# CMoy-Pro-V_0_0_1A.net
KiCad netlist of a schematic drawn in EAGLE
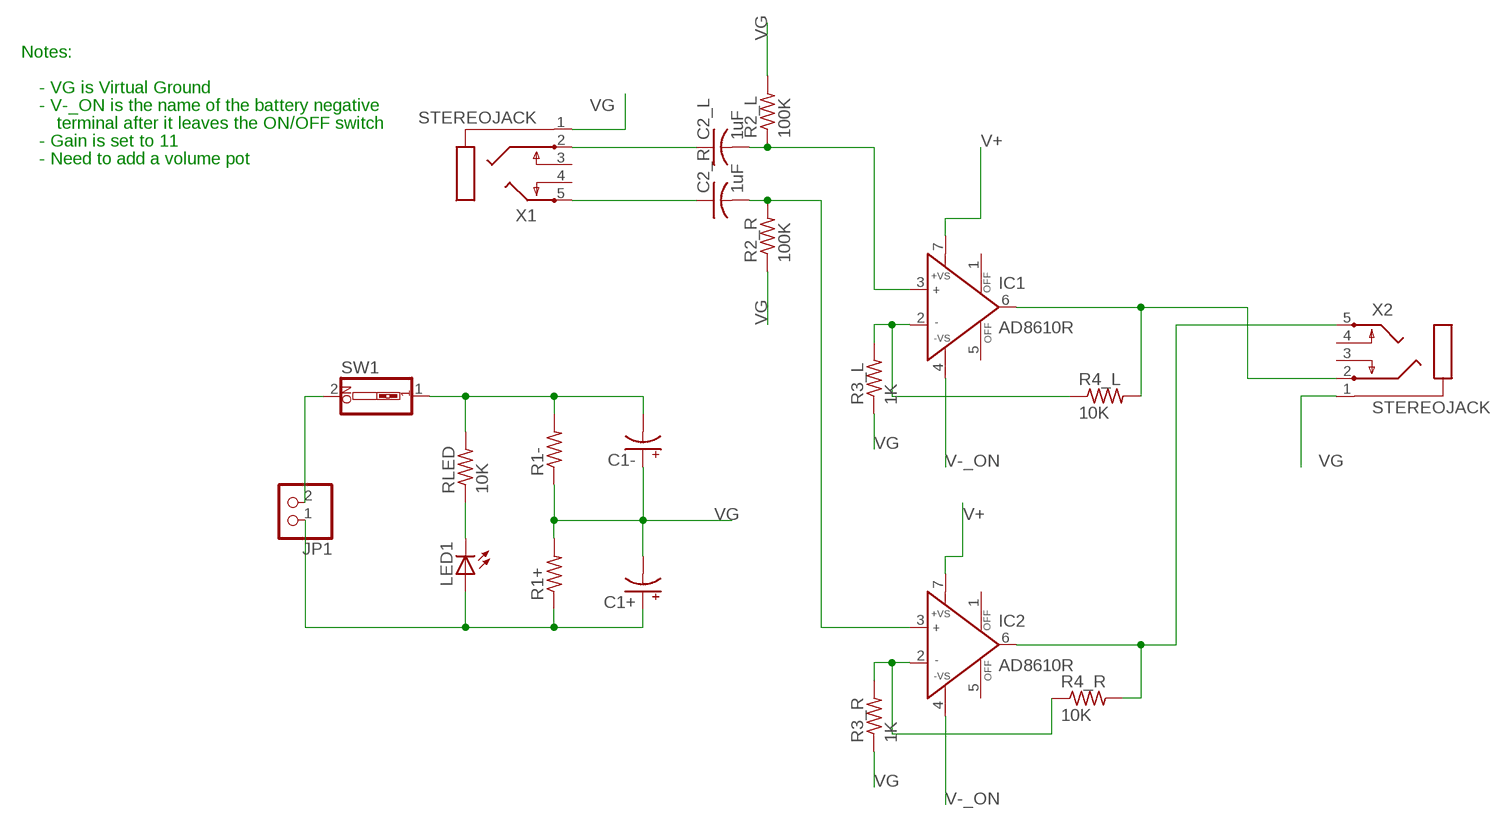
[diagram p0: schematic, sheet 1]

(export (version "E")
  (design (tool "Eeschema 10.0.6"))
  (components
    (comp (ref "C1+")
      (value "CPOL-USE2.5-6")
      (footprint "eagle-import:E2,5-6")
      (libsource (lib "eagle-import") (part "CPOL-USE2.5-6"))
    )
    (comp (ref "C1-")
      (value "CPOL-USE2.5-6")
      (footprint "eagle-import:E2,5-6")
      (libsource (lib "eagle-import") (part "CPOL-USE2.5-6"))
    )
    (comp (ref "C2_L")
      (value "1uF")
      (footprint "eagle-import:C102-043X133")
      (libsource (lib "eagle-import") (part "C-US102-043X133"))
    )
    (comp (ref "C2_R")
      (value "1uF")
      (footprint "eagle-import:C102-043X133")
      (libsource (lib "eagle-import") (part "C-US102-043X133"))
    )
    (comp (ref "IC1")
      (value "AD8610R")
      (footprint "eagle-import:SO8")
      (fields (field (name "MF") "ALTERA CORPORATION") (field (name "MPN") "AD8610BRZ"))
      (libsource (lib "eagle-import") (part "AD8610R"))
    )
    (comp (ref "IC2")
      (value "AD8610R")
      (footprint "eagle-import:SO8")
      (fields (field (name "MF") "ALTERA CORPORATION") (field (name "MPN") "AD8610BRZ"))
      (libsource (lib "eagle-import") (part "AD8610R"))
    )
    (comp (ref "JP1")
      (value "PINHD-1X2")
      (footprint "eagle-import:1X02")
      (libsource (lib "eagle-import") (part "PINHD-1X2"))
    )
    (comp (ref "LED1")
      (value "LED3MM")
      (footprint "eagle-import:LED3MM")
      (libsource (lib "eagle-import") (part "LED3MM"))
    )
    (comp (ref "R1+")
      (value "R-US_0207/7")
      (footprint "eagle-import:0207_7")
      (libsource (lib "eagle-import") (part "R-US_0207/7"))
    )
    (comp (ref "R1-")
      (value "R-US_0207/7")
      (footprint "eagle-import:0207_7")
      (libsource (lib "eagle-import") (part "R-US_0207/7"))
    )
    (comp (ref "R2_L")
      (value "100K")
      (footprint "eagle-import:0207_7")
      (libsource (lib "eagle-import") (part "R-US_0207/7"))
    )
    (comp (ref "R2_R")
      (value "100K")
      (footprint "eagle-import:0207_7")
      (libsource (lib "eagle-import") (part "R-US_0207/7"))
    )
    (comp (ref "R3_L")
      (value "1K")
      (footprint "eagle-import:0207_7")
      (libsource (lib "eagle-import") (part "R-US_0207/7"))
    )
    (comp (ref "R3_R")
      (value "1K")
      (footprint "eagle-import:0207_7")
      (libsource (lib "eagle-import") (part "R-US_0207/7"))
    )
    (comp (ref "R4_L")
      (value "10K")
      (footprint "eagle-import:0207_7")
      (libsource (lib "eagle-import") (part "R-US_0207/7"))
    )
    (comp (ref "R4_R")
      (value "10K")
      (footprint "eagle-import:0207_7")
      (libsource (lib "eagle-import") (part "R-US_0207/7"))
    )
    (comp (ref "RLED")
      (value "10K")
      (footprint "eagle-import:0207_7")
      (libsource (lib "eagle-import") (part "R-US_0207/7"))
    )
    (comp (ref "SW1")
      (value "SW_DIP-1")
      (footprint "eagle-import:EDG-01")
      (libsource (lib "eagle-import") (part "SW_DIP-1"))
    )
    (comp (ref "X1")
      (value "STEREOJACK")
      (footprint "eagle-import:STX3100")
      (libsource (lib "eagle-import") (part "STEREOJACK"))
    )
    (comp (ref "X2")
      (value "STEREOJACK")
      (footprint "eagle-import:STX3100")
      (libsource (lib "eagle-import") (part "STEREOJACK"))
    )
  )
  (nets
    (net (code "1") (name "/V+") (class "Default")
      (node (ref "C1+") (pin "+") (pinfunction "+_+") (pintype "passive"))
      (node (ref "IC1") (pin "7") (pinfunction "+VS_7") (pintype "input"))
      (node (ref "IC2") (pin "7") (pinfunction "+VS_7") (pintype "input"))
      (node (ref "JP1") (pin "1") (pinfunction "1_1") (pintype "passive"))
      (node (ref "LED1") (pin "A") (pinfunction "A_A") (pintype "passive"))
      (node (ref "R1+") (pin "1") (pinfunction "1_1") (pintype "passive"))
    )
    (net (code "2") (name "/V-_ON") (class "Default")
      (node (ref "C1-") (pin "-") (pinfunction "-_-") (pintype "passive"))
      (node (ref "IC1") (pin "4") (pinfunction "-VS_4") (pintype "input"))
      (node (ref "IC2") (pin "4") (pinfunction "-VS_4") (pintype "input"))
      (node (ref "R1-") (pin "2") (pinfunction "2_2") (pintype "passive"))
      (node (ref "RLED") (pin "2") (pinfunction "2_2") (pintype "passive"))
      (node (ref "SW1") (pin "1") (pinfunction "1_1") (pintype "passive"))
    )
    (net (code "3") (name "/VG") (class "Default")
      (node (ref "C1+") (pin "-") (pinfunction "-_-") (pintype "passive"))
      (node (ref "C1-") (pin "+") (pinfunction "+_+") (pintype "passive"))
      (node (ref "R1+") (pin "2") (pinfunction "2_2") (pintype "passive"))
      (node (ref "R1-") (pin "1") (pinfunction "1_1") (pintype "passive"))
      (node (ref "R2_L") (pin "2") (pinfunction "2_2") (pintype "passive"))
      (node (ref "R2_R") (pin "1") (pinfunction "1_1") (pintype "passive"))
      (node (ref "R3_L") (pin "1") (pinfunction "1_1") (pintype "passive"))
      (node (ref "R3_R") (pin "1") (pinfunction "1_1") (pintype "passive"))
      (node (ref "X1") (pin "1") (pinfunction "1_1") (pintype "passive"))
      (node (ref "X2") (pin "1") (pinfunction "1_1") (pintype "passive"))
    )
    (net (code "4") (name "Net-(C2_L-Pad1)") (class "Default")
      (node (ref "C2_L") (pin "1") (pinfunction "1_1") (pintype "passive"))
      (node (ref "X1") (pin "2") (pinfunction "2_2") (pintype "passive"))
    )
    (net (code "5") (name "Net-(C2_R-Pad1)") (class "Default")
      (node (ref "C2_R") (pin "1") (pinfunction "1_1") (pintype "passive"))
      (node (ref "X1") (pin "5") (pinfunction "5_5") (pintype "passive"))
    )
    (net (code "6") (name "Net-(IC1-IN+)") (class "Default")
      (node (ref "C2_L") (pin "2") (pinfunction "2_2") (pintype "passive"))
      (node (ref "IC1") (pin "3") (pinfunction "IN+_3") (pintype "input"))
      (node (ref "R2_L") (pin "1") (pinfunction "1_1") (pintype "passive"))
    )
    (net (code "7") (name "Net-(IC1-IN-)") (class "Default")
      (node (ref "IC1") (pin "2") (pinfunction "IN-_2") (pintype "input"))
      (node (ref "R3_L") (pin "2") (pinfunction "2_2") (pintype "passive"))
      (node (ref "R4_L") (pin "1") (pinfunction "1_1") (pintype "passive"))
    )
    (net (code "8") (name "Net-(IC1-OUT)") (class "Default")
      (node (ref "IC1") (pin "6") (pinfunction "OUT_6") (pintype "output"))
      (node (ref "R4_L") (pin "2") (pinfunction "2_2") (pintype "passive"))
      (node (ref "X2") (pin "2") (pinfunction "2_2") (pintype "passive"))
    )
    (net (code "9") (name "Net-(IC2-IN+)") (class "Default")
      (node (ref "C2_R") (pin "2") (pinfunction "2_2") (pintype "passive"))
      (node (ref "IC2") (pin "3") (pinfunction "IN+_3") (pintype "input"))
      (node (ref "R2_R") (pin "2") (pinfunction "2_2") (pintype "passive"))
    )
    (net (code "10") (name "Net-(IC2-IN-)") (class "Default")
      (node (ref "IC2") (pin "2") (pinfunction "IN-_2") (pintype "input"))
      (node (ref "R3_R") (pin "2") (pinfunction "2_2") (pintype "passive"))
      (node (ref "R4_R") (pin "1") (pinfunction "1_1") (pintype "passive"))
    )
    (net (code "11") (name "Net-(IC2-OUT)") (class "Default")
      (node (ref "IC2") (pin "6") (pinfunction "OUT_6") (pintype "output"))
      (node (ref "R4_R") (pin "2") (pinfunction "2_2") (pintype "passive"))
      (node (ref "X2") (pin "5") (pinfunction "5_5") (pintype "passive"))
    )
    (net (code "12") (name "Net-(JP1-Pad2)") (class "Default")
      (node (ref "JP1") (pin "2") (pinfunction "2_2") (pintype "passive"))
      (node (ref "SW1") (pin "2") (pinfunction "2_2") (pintype "passive"))
    )
    (net (code "13") (name "Net-(LED1-C)") (class "Default")
      (node (ref "LED1") (pin "K") (pinfunction "C_K") (pintype "passive"))
      (node (ref "RLED") (pin "1") (pinfunction "1_1") (pintype "passive"))
    )
    (net (code "14") (name "unconnected-(IC1-OFF-Pad1)") (class "Default")
      (node (ref "IC1") (pin "1") (pinfunction "OFF_1") (pintype "passive"))
    )
    (net (code "15") (name "unconnected-(IC1-OFF-Pad5)") (class "Default")
      (node (ref "IC1") (pin "5") (pinfunction "OFF_5") (pintype "passive"))
    )
    (net (code "16") (name "unconnected-(IC2-OFF-Pad1)") (class "Default")
      (node (ref "IC2") (pin "1") (pinfunction "OFF_1") (pintype "passive"))
    )
    (net (code "17") (name "unconnected-(IC2-OFF-Pad5)") (class "Default")
      (node (ref "IC2") (pin "5") (pinfunction "OFF_5") (pintype "passive"))
    )
    (net (code "18") (name "unconnected-(X1-Pad3)") (class "Default")
      (node (ref "X1") (pin "3") (pinfunction "3_3") (pintype "passive"))
    )
    (net (code "19") (name "unconnected-(X1-Pad4)") (class "Default")
      (node (ref "X1") (pin "4") (pinfunction "4_4") (pintype "passive"))
    )
    (net (code "20") (name "unconnected-(X2-Pad3)") (class "Default")
      (node (ref "X2") (pin "3") (pinfunction "3_3") (pintype "passive"))
    )
    (net (code "21") (name "unconnected-(X2-Pad4)") (class "Default")
      (node (ref "X2") (pin "4") (pinfunction "4_4") (pintype "passive"))
    )
  )
)
